# Risha_Mega_Shield.net
KiCad netlist of a schematic drawn in EAGLE
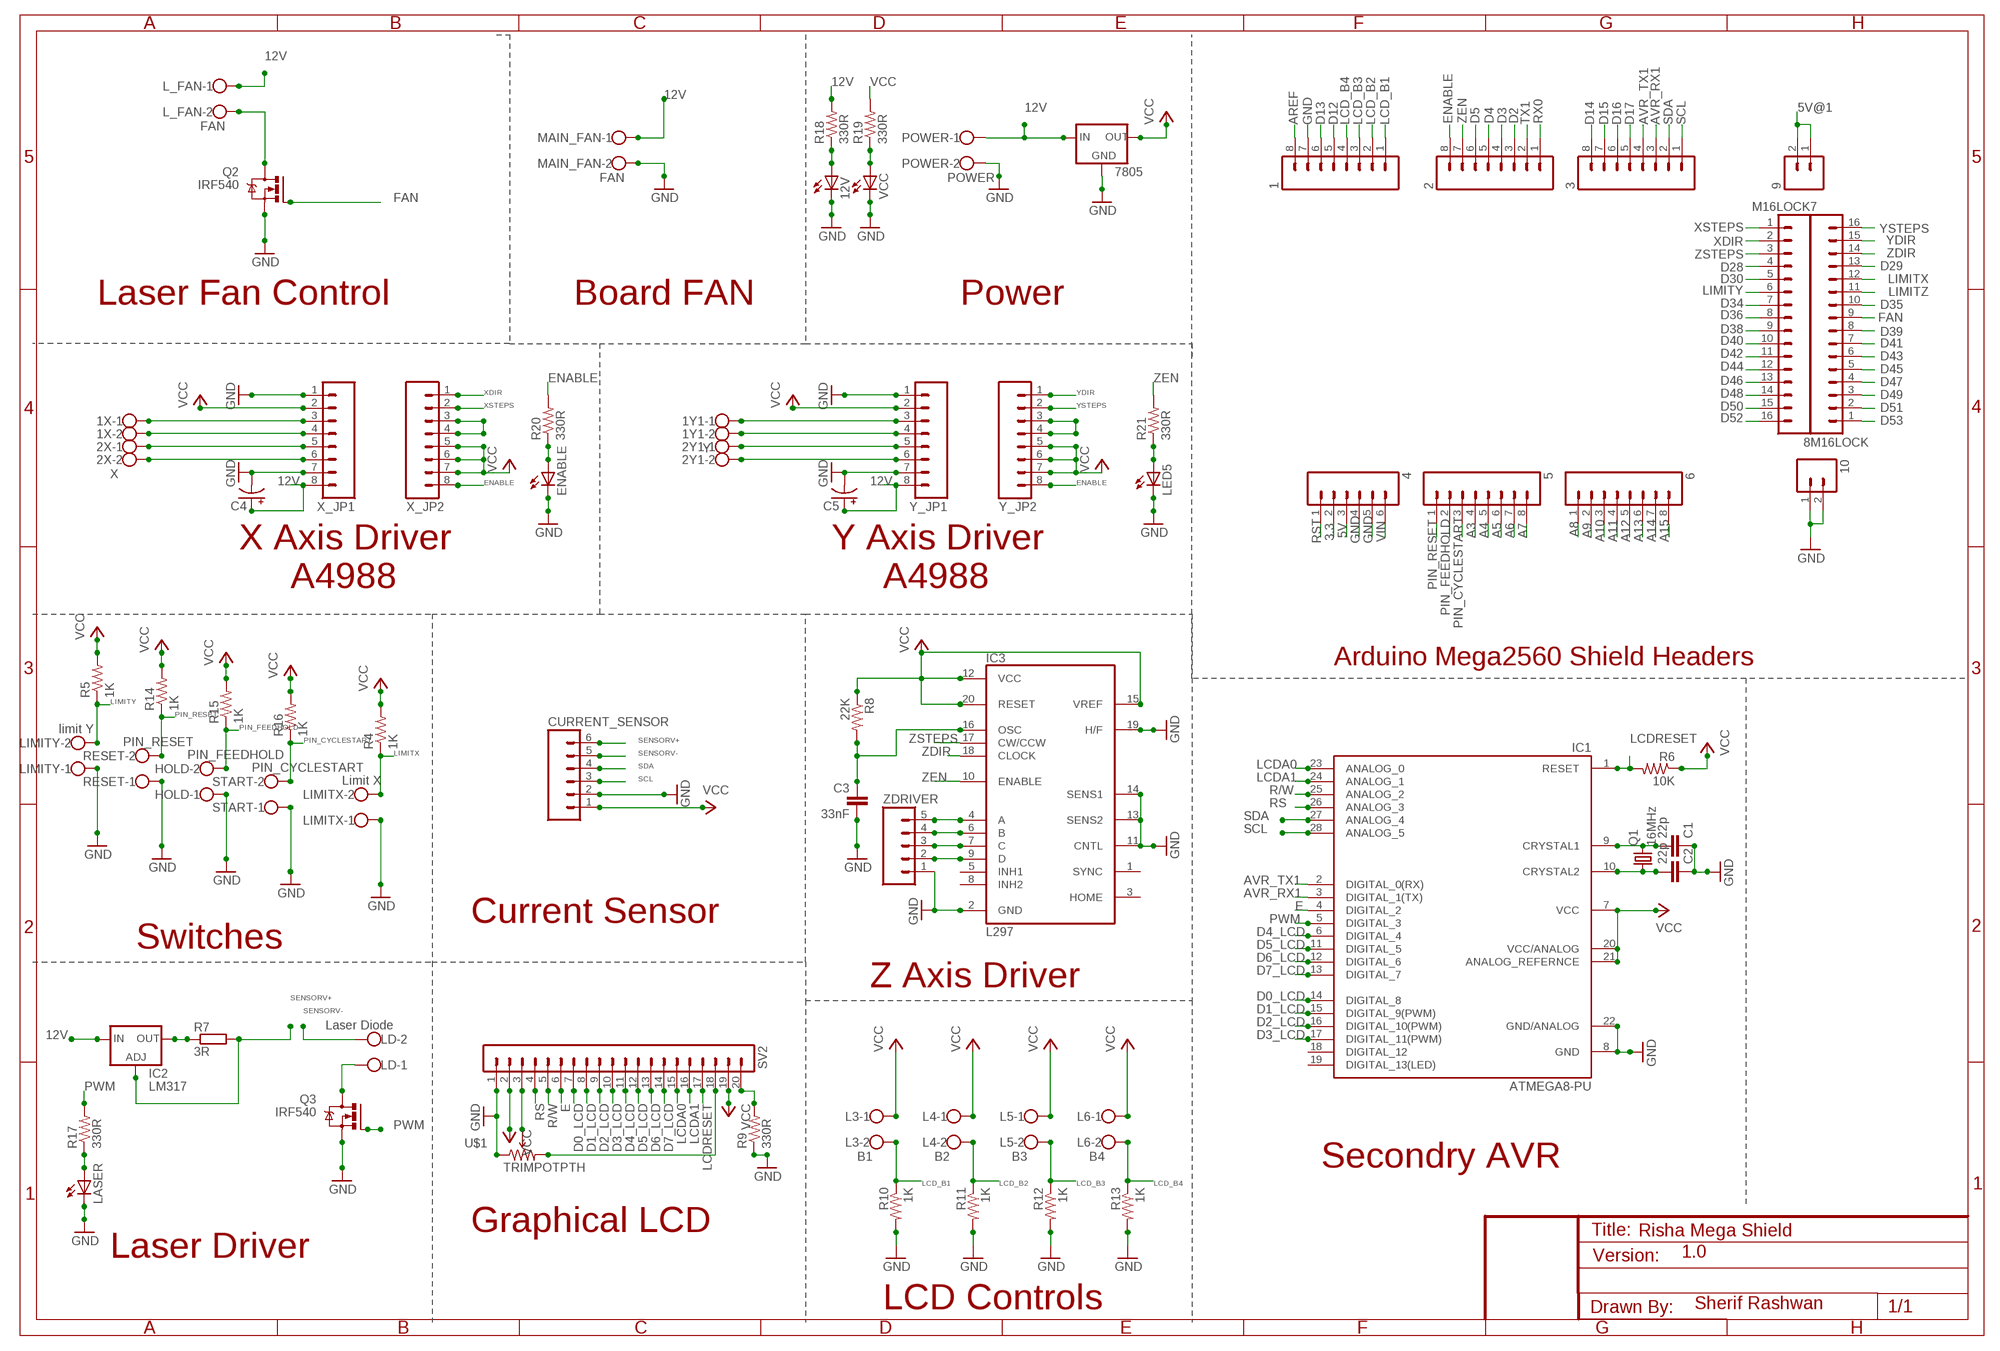
[diagram p0: schematic, sheet 1]

(export (version "E")
  (design (tool "Eeschema 10.0.6"))
  (components
    (comp (ref "1")
      (value "M08LOCK")
      (footprint "eagle-import:1X08_LOCK")
      (libsource (lib "eagle-import") (part "SparkFun_M08LOCK"))
    )
    (comp (ref "1X")
      (value "W237-102")
      (footprint "eagle-import:W237-102")
      (fields (field (name "MPN") "237-102"))
      (libsource (lib "eagle-import") (part "W237-102"))
    )
    (comp (ref "1Y1")
      (value "Y")
      (footprint "eagle-import:W237-102")
      (fields (field (name "MPN") "237-102"))
      (libsource (lib "eagle-import") (part "W237-102"))
    )
    (comp (ref "2")
      (value "M08LOCK")
      (footprint "eagle-import:1X08_LOCK")
      (libsource (lib "eagle-import") (part "SparkFun_M08LOCK"))
    )
    (comp (ref "2X")
      (value "X")
      (footprint "eagle-import:W237-102")
      (fields (field (name "MPN") "237-102"))
      (libsource (lib "eagle-import") (part "W237-102"))
    )
    (comp (ref "2Y1")
      (value "W237-102")
      (footprint "eagle-import:W237-102")
      (fields (field (name "MPN") "237-102"))
      (libsource (lib "eagle-import") (part "W237-102"))
    )
    (comp (ref "3")
      (value "M08LOCK")
      (footprint "eagle-import:1X08_LOCK")
      (libsource (lib "eagle-import") (part "SparkFun_M08LOCK"))
    )
    (comp (ref "4")
      (value "M06LOCK")
      (footprint "eagle-import:1X06_LOCK")
      (libsource (lib "eagle-import") (part "SparkFun_M06LOCK"))
    )
    (comp (ref "5")
      (value "M08LOCK")
      (footprint "eagle-import:1X08_LOCK")
      (libsource (lib "eagle-import") (part "SparkFun_M08LOCK"))
    )
    (comp (ref "6")
      (value "M08LOCK")
      (footprint "eagle-import:1X08_LOCK")
      (libsource (lib "eagle-import") (part "SparkFun_M08LOCK"))
    )
    (comp (ref "7")
      (value "M16LOCK")
      (footprint "eagle-import:1X16_LOCK")
      (libsource (lib "eagle-import") (part "M16LOCK"))
    )
    (comp (ref "8")
      (value "M16LOCK")
      (footprint "eagle-import:1X16_LOCK")
      (libsource (lib "eagle-import") (part "M16LOCK"))
    )
    (comp (ref "9")
      (value "M02LOCK")
      (footprint "eagle-import:1X02_LOCK")
      (libsource (lib "eagle-import") (part "M02LOCK"))
    )
    (comp (ref "10")
      (value "M02LOCK")
      (footprint "eagle-import:1X02_LOCK")
      (libsource (lib "eagle-import") (part "M02LOCK"))
    )
    (comp (ref "12V")
      (value "LED3MM")
      (footprint "eagle-import:LED3MM")
      (libsource (lib "eagle-import") (part "LED3MM"))
    )
    (comp (ref "7805")
      (value "V_REG_78XXSINK")
      (footprint "eagle-import:TO220-IGO")
      (libsource (lib "eagle-import") (part "V_REG_78XXSINK"))
    )
    (comp (ref "C1")
      (value "22p")
      (footprint "eagle-import:C2.5-2")
      (libsource (lib "eagle-import") (part "C2.5/2"))
    )
    (comp (ref "C2")
      (value "22p")
      (footprint "eagle-import:C2.5-2")
      (libsource (lib "eagle-import") (part "C2.5/2"))
    )
    (comp (ref "C3")
      (value "33nF")
      (footprint "eagle-import:C2.5-2")
      (libsource (lib "eagle-import") (part "C2.5/2"))
    )
    (comp (ref "C4")
      (value "CAP_POLPTH2")
      (footprint "eagle-import:CPOL-RADIAL-10UF-25V")
      (libsource (lib "eagle-import") (part "CAP_POLPTH2"))
    )
    (comp (ref "C5")
      (value "CAP_POLPTH2")
      (footprint "eagle-import:CPOL-RADIAL-10UF-25V")
      (libsource (lib "eagle-import") (part "CAP_POLPTH2"))
    )
    (comp (ref "CURRENT_SENSOR")
      (value "M06LONGPADS")
      (footprint "eagle-import:1X06_LONGPADS")
      (libsource (lib "eagle-import") (part "M06LONGPADS"))
    )
    (comp (ref "ENABLE")
      (value "LED3MM")
      (footprint "eagle-import:LED3MM")
      (libsource (lib "eagle-import") (part "LED3MM"))
    )
    (comp (ref "HOLD")
      (value "PIN_FEEDHOLD")
      (footprint "eagle-import:W237-102")
      (fields (field (name "MPN") "237-102"))
      (libsource (lib "eagle-import") (part "W237-102"))
    )
    (comp (ref "IC1")
      (value "ATMEGA8-PU")
      (footprint "eagle-import:DIL28-3")
      (libsource (lib "eagle-import") (part "ATMEGA8-PU"))
    )
    (comp (ref "IC2")
      (value "LM317")
      (footprint "eagle-import:TO3-K02")
      (libsource (lib "eagle-import") (part "LM317-TO3"))
    )
    (comp (ref "IC3")
      (value "L297")
      (footprint "eagle-import:DIL20")
      (fields (field (name "MPN") "L297/1"))
      (libsource (lib "eagle-import") (part "L297"))
    )
    (comp (ref "L3")
      (value "B1")
      (footprint "eagle-import:W237-102")
      (fields (field (name "MPN") "237-102"))
      (libsource (lib "eagle-import") (part "W237-102"))
    )
    (comp (ref "L4")
      (value "B2")
      (footprint "eagle-import:W237-102")
      (fields (field (name "MPN") "237-102"))
      (libsource (lib "eagle-import") (part "W237-102"))
    )
    (comp (ref "L5")
      (value "B3")
      (footprint "eagle-import:W237-102")
      (fields (field (name "MPN") "237-102"))
      (libsource (lib "eagle-import") (part "W237-102"))
    )
    (comp (ref "L6")
      (value "B4")
      (footprint "eagle-import:W237-102")
      (fields (field (name "MPN") "237-102"))
      (libsource (lib "eagle-import") (part "W237-102"))
    )
    (comp (ref "LASER")
      (value "LED3MM")
      (footprint "eagle-import:LED3MM")
      (libsource (lib "eagle-import") (part "LED3MM"))
    )
    (comp (ref "LD")
      (value "Laser Diode")
      (footprint "eagle-import:W237-102")
      (fields (field (name "MPN") "237-102"))
      (libsource (lib "eagle-import") (part "W237-102"))
    )
    (comp (ref "LED5")
      (value "LED3MM")
      (footprint "eagle-import:LED3MM")
      (libsource (lib "eagle-import") (part "LED3MM"))
    )
    (comp (ref "LIMITX")
      (value "Limit X")
      (footprint "eagle-import:W237-102")
      (fields (field (name "MPN") "237-102"))
      (libsource (lib "eagle-import") (part "W237-102"))
    )
    (comp (ref "LIMITY")
      (value "limit Y")
      (footprint "eagle-import:W237-102")
      (fields (field (name "MPN") "237-102"))
      (libsource (lib "eagle-import") (part "W237-102"))
    )
    (comp (ref "L_FAN")
      (value "FAN")
      (footprint "eagle-import:W237-102")
      (fields (field (name "MPN") "237-102"))
      (libsource (lib "eagle-import") (part "W237-102"))
    )
    (comp (ref "MAIN_FAN")
      (value "FAN")
      (footprint "eagle-import:W237-102")
      (fields (field (name "MPN") "237-102"))
      (libsource (lib "eagle-import") (part "W237-102"))
    )
    (comp (ref "POWER")
      (value "POWER")
      (footprint "eagle-import:W237-102")
      (fields (field (name "MPN") "237-102"))
      (libsource (lib "eagle-import") (part "W237-102"))
    )
    (comp (ref "Q1")
      (value "16MHz")
      (footprint "eagle-import:HC49US")
      (libsource (lib "eagle-import") (part "CRYSTALHC49US"))
    )
    (comp (ref "Q2")
      (value "IRF540")
      (footprint "eagle-import:TO220BV")
      (libsource (lib "eagle-import") (part "IRF540"))
    )
    (comp (ref "Q3")
      (value "IRF540")
      (footprint "eagle-import:TO220BV")
      (libsource (lib "eagle-import") (part "IRF540"))
    )
    (comp (ref "R4")
      (value "1K")
      (footprint "eagle-import:1_6W-RES")
      (libsource (lib "eagle-import") (part "RESISTORPTH-1/6W"))
    )
    (comp (ref "R5")
      (value "1K")
      (footprint "eagle-import:1_6W-RES")
      (libsource (lib "eagle-import") (part "RESISTORPTH-1/6W"))
    )
    (comp (ref "R6")
      (value "10K")
      (footprint "eagle-import:1_6W-RES")
      (libsource (lib "eagle-import") (part "RESISTORPTH-1/6W"))
    )
    (comp (ref "R7")
      (value "3R")
      (footprint "eagle-import:0309_12")
      (libsource (lib "eagle-import") (part "R-EU_0309/12"))
    )
    (comp (ref "R8")
      (value "22K")
      (footprint "eagle-import:1_6W-RES")
      (libsource (lib "eagle-import") (part "RESISTORPTH-1/6W"))
    )
    (comp (ref "R9")
      (value "330R")
      (footprint "eagle-import:1_6W-RES")
      (libsource (lib "eagle-import") (part "RESISTORPTH-1/6W"))
    )
    (comp (ref "R10")
      (value "1K")
      (footprint "eagle-import:1_6W-RES")
      (libsource (lib "eagle-import") (part "RESISTORPTH-1/6W"))
    )
    (comp (ref "R11")
      (value "1K")
      (footprint "eagle-import:1_6W-RES")
      (libsource (lib "eagle-import") (part "RESISTORPTH-1/6W"))
    )
    (comp (ref "R12")
      (value "1K")
      (footprint "eagle-import:1_6W-RES")
      (libsource (lib "eagle-import") (part "RESISTORPTH-1/6W"))
    )
    (comp (ref "R13")
      (value "1K")
      (footprint "eagle-import:1_6W-RES")
      (libsource (lib "eagle-import") (part "RESISTORPTH-1/6W"))
    )
    (comp (ref "R14")
      (value "1K")
      (footprint "eagle-import:1_6W-RES")
      (libsource (lib "eagle-import") (part "RESISTORPTH-1/6W"))
    )
    (comp (ref "R15")
      (value "1K")
      (footprint "eagle-import:1_6W-RES")
      (libsource (lib "eagle-import") (part "RESISTORPTH-1/6W"))
    )
    (comp (ref "R16")
      (value "1K")
      (footprint "eagle-import:1_6W-RES")
      (libsource (lib "eagle-import") (part "RESISTORPTH-1/6W"))
    )
    (comp (ref "R17")
      (value "330R")
      (footprint "eagle-import:1_6W-RES")
      (libsource (lib "eagle-import") (part "RESISTORPTH-1/6W"))
    )
    (comp (ref "R18")
      (value "330R")
      (footprint "eagle-import:1_6W-RES")
      (libsource (lib "eagle-import") (part "RESISTORPTH-1/6W"))
    )
    (comp (ref "R19")
      (value "330R")
      (footprint "eagle-import:1_6W-RES")
      (libsource (lib "eagle-import") (part "RESISTORPTH-1/6W"))
    )
    (comp (ref "R20")
      (value "330R")
      (footprint "eagle-import:1_6W-RES")
      (libsource (lib "eagle-import") (part "RESISTORPTH-1/6W"))
    )
    (comp (ref "R21")
      (value "330R")
      (footprint "eagle-import:1_6W-RES")
      (libsource (lib "eagle-import") (part "RESISTORPTH-1/6W"))
    )
    (comp (ref "RESET")
      (value "PIN_RESET")
      (footprint "eagle-import:W237-102")
      (fields (field (name "MPN") "237-102"))
      (libsource (lib "eagle-import") (part "W237-102"))
    )
    (comp (ref "START")
      (value "PIN_CYCLESTART")
      (footprint "eagle-import:W237-102")
      (fields (field (name "MPN") "237-102"))
      (libsource (lib "eagle-import") (part "W237-102"))
    )
    (comp (ref "SV2")
      (value "MA20-1W")
      (footprint "eagle-import:MA20-1W")
      (libsource (lib "eagle-import") (part "MA20-1W"))
    )
    (comp (ref "U$1")
      (value "TRIMPOTPTH")
      (footprint "eagle-import:TRIM_POT_PTH")
      (libsource (lib "eagle-import") (part "TRIMPOTPTH"))
    )
    (comp (ref "VCC")
      (value "LED3MM")
      (footprint "eagle-import:LED3MM")
      (libsource (lib "eagle-import") (part "LED3MM"))
    )
    (comp (ref "X_JP1")
      (value "M08")
      (footprint "eagle-import:1X08")
      (libsource (lib "eagle-import") (part "M08"))
    )
    (comp (ref "X_JP2")
      (value "M08")
      (footprint "eagle-import:1X08")
      (libsource (lib "eagle-import") (part "M08"))
    )
    (comp (ref "Y_JP1")
      (value "M08")
      (footprint "eagle-import:1X08")
      (libsource (lib "eagle-import") (part "M08"))
    )
    (comp (ref "Y_JP2")
      (value "M08")
      (footprint "eagle-import:1X08")
      (libsource (lib "eagle-import") (part "M08"))
    )
    (comp (ref "ZDRIVER")
      (value "M05PTH_LONGPADS")
      (footprint "eagle-import:1X05_LONGPADS")
      (libsource (lib "eagle-import") (part "M05PTH_LONGPADS"))
    )
  )
  (nets
    (net (code "1") (name "/3.3") (class "Default")
      (node (ref "4") (pin "2") (pinfunction "2_2") (pintype "passive"))
    )
    (net (code "2") (name "/5V") (class "Default")
      (node (ref "4") (pin "3") (pinfunction "3_3") (pintype "passive"))
    )
    (net (code "3") (name "/5V@1") (class "Default")
      (node (ref "9") (pin "1") (pinfunction "1_1") (pintype "passive"))
      (node (ref "9") (pin "2") (pinfunction "2_2") (pintype "passive"))
    )
    (net (code "4") (name "/12V") (class "Default")
      (node (ref "7805") (pin "IN") (pinfunction "IN_IN") (pintype "input"))
      (node (ref "C4") (pin "1") (pinfunction "+_1") (pintype "passive"))
      (node (ref "C5") (pin "1") (pinfunction "+_1") (pintype "passive"))
      (node (ref "IC2") (pin "1") (pinfunction "IN_1") (pintype "input"))
      (node (ref "L_FAN") (pin "1") (pinfunction "KL_1") (pintype "passive"))
      (node (ref "MAIN_FAN") (pin "1") (pinfunction "KL_1") (pintype "passive"))
      (node (ref "POWER") (pin "1") (pinfunction "KL_1") (pintype "passive"))
      (node (ref "R18") (pin "2") (pinfunction "2_2") (pintype "passive"))
      (node (ref "X_JP1") (pin "8") (pinfunction "8_8") (pintype "passive"))
      (node (ref "Y_JP1") (pin "8") (pinfunction "8_8") (pintype "passive"))
    )
    (net (code "5") (name "/A3") (class "Default")
      (node (ref "5") (pin "4") (pinfunction "4_4") (pintype "passive"))
    )
    (net (code "6") (name "/A4") (class "Default")
      (node (ref "5") (pin "5") (pinfunction "5_5") (pintype "passive"))
    )
    (net (code "7") (name "/A5") (class "Default")
      (node (ref "5") (pin "6") (pinfunction "6_6") (pintype "passive"))
    )
    (net (code "8") (name "/A6") (class "Default")
      (node (ref "5") (pin "7") (pinfunction "7_7") (pintype "passive"))
    )
    (net (code "9") (name "/A7") (class "Default")
      (node (ref "5") (pin "8") (pinfunction "8_8") (pintype "passive"))
    )
    (net (code "10") (name "/A8") (class "Default")
      (node (ref "6") (pin "1") (pinfunction "1_1") (pintype "passive"))
    )
    (net (code "11") (name "/A9") (class "Default")
      (node (ref "6") (pin "2") (pinfunction "2_2") (pintype "passive"))
    )
    (net (code "12") (name "/A10") (class "Default")
      (node (ref "6") (pin "3") (pinfunction "3_3") (pintype "passive"))
    )
    (net (code "13") (name "/A11") (class "Default")
      (node (ref "6") (pin "4") (pinfunction "4_4") (pintype "passive"))
    )
    (net (code "14") (name "/A12") (class "Default")
      (node (ref "6") (pin "5") (pinfunction "5_5") (pintype "passive"))
    )
    (net (code "15") (name "/A13") (class "Default")
      (node (ref "6") (pin "6") (pinfunction "6_6") (pintype "passive"))
    )
    (net (code "16") (name "/A14") (class "Default")
      (node (ref "6") (pin "7") (pinfunction "7_7") (pintype "passive"))
    )
    (net (code "17") (name "/A15") (class "Default")
      (node (ref "6") (pin "8") (pinfunction "8_8") (pintype "passive"))
    )
    (net (code "18") (name "/AREF") (class "Default")
      (node (ref "1") (pin "8") (pinfunction "8_8") (pintype "passive"))
    )
    (net (code "19") (name "/AVR_RX1") (class "Default")
      (node (ref "3") (pin "3") (pinfunction "3_3") (pintype "passive"))
      (node (ref "IC1") (pin "3") (pinfunction "DIGITAL_1(TX)_3") (pintype "bidirectional"))
    )
    (net (code "20") (name "/AVR_TX1") (class "Default")
      (node (ref "3") (pin "4") (pinfunction "4_4") (pintype "passive"))
      (node (ref "IC1") (pin "2") (pinfunction "DIGITAL_0(RX)_2") (pintype "bidirectional"))
    )
    (net (code "21") (name "/D0_LCD") (class "Default")
      (node (ref "IC1") (pin "14") (pinfunction "DIGITAL_8_14") (pintype "bidirectional"))
      (node (ref "SV2") (pin "7") (pinfunction "7_7") (pintype "passive"))
    )
    (net (code "22") (name "/D1_LCD") (class "Default")
      (node (ref "IC1") (pin "15") (pinfunction "DIGITAL_9(PWM)_15") (pintype "bidirectional"))
      (node (ref "SV2") (pin "8") (pinfunction "8_8") (pintype "passive"))
    )
    (net (code "23") (name "/D2") (class "Default")
      (node (ref "2") (pin "3") (pinfunction "3_3") (pintype "passive"))
    )
    (net (code "24") (name "/D2_LCD") (class "Default")
      (node (ref "IC1") (pin "16") (pinfunction "DIGITAL_10(PWM)_16") (pintype "bidirectional"))
      (node (ref "SV2") (pin "9") (pinfunction "9_9") (pintype "passive"))
    )
    (net (code "25") (name "/D3") (class "Default")
      (node (ref "2") (pin "4") (pinfunction "4_4") (pintype "passive"))
    )
    (net (code "26") (name "/D3_LCD") (class "Default")
      (node (ref "IC1") (pin "17") (pinfunction "DIGITAL_11(PWM)_17") (pintype "bidirectional"))
      (node (ref "SV2") (pin "10") (pinfunction "10_10") (pintype "passive"))
    )
    (net (code "27") (name "/D4") (class "Default")
      (node (ref "2") (pin "5") (pinfunction "5_5") (pintype "passive"))
    )
    (net (code "28") (name "/D4_LCD") (class "Default")
      (node (ref "IC1") (pin "6") (pinfunction "DIGITAL_4_6") (pintype "bidirectional"))
      (node (ref "SV2") (pin "11") (pinfunction "11_11") (pintype "passive"))
    )
    (net (code "29") (name "/D5") (class "Default")
      (node (ref "2") (pin "6") (pinfunction "6_6") (pintype "passive"))
    )
    (net (code "30") (name "/D5_LCD") (class "Default")
      (node (ref "IC1") (pin "11") (pinfunction "DIGITAL_5_11") (pintype "bidirectional"))
      (node (ref "SV2") (pin "12") (pinfunction "12_12") (pintype "passive"))
    )
    (net (code "31") (name "/D6_LCD") (class "Default")
      (node (ref "IC1") (pin "12") (pinfunction "DIGITAL_6_12") (pintype "bidirectional"))
      (node (ref "SV2") (pin "13") (pinfunction "13_13") (pintype "passive"))
    )
    (net (code "32") (name "/D7_LCD") (class "Default")
      (node (ref "IC1") (pin "13") (pinfunction "DIGITAL_7_13") (pintype "bidirectional"))
      (node (ref "SV2") (pin "14") (pinfunction "14_14") (pintype "passive"))
    )
    (net (code "33") (name "/D12") (class "Default")
      (node (ref "1") (pin "5") (pinfunction "5_5") (pintype "passive"))
    )
    (net (code "34") (name "/D13") (class "Default")
      (node (ref "1") (pin "6") (pinfunction "6_6") (pintype "passive"))
    )
    (net (code "35") (name "/D14") (class "Default")
      (node (ref "3") (pin "8") (pinfunction "8_8") (pintype "passive"))
    )
    (net (code "36") (name "/D15") (class "Default")
      (node (ref "3") (pin "7") (pinfunction "7_7") (pintype "passive"))
    )
    (net (code "37") (name "/D16") (class "Default")
      (node (ref "3") (pin "6") (pinfunction "6_6") (pintype "passive"))
    )
    (net (code "38") (name "/D17") (class "Default")
      (node (ref "3") (pin "5") (pinfunction "5_5") (pintype "passive"))
    )
    (net (code "39") (name "/D28") (class "Default")
      (node (ref "8") (pin "4") (pinfunction "4_4") (pintype "passive"))
    )
    (net (code "40") (name "/D29") (class "Default")
      (node (ref "7") (pin "13") (pinfunction "13_13") (pintype "passive"))
    )
    (net (code "41") (name "/D30") (class "Default")
      (node (ref "8") (pin "5") (pinfunction "5_5") (pintype "passive"))
    )
    (net (code "42") (name "/D34") (class "Default")
      (node (ref "8") (pin "7") (pinfunction "7_7") (pintype "passive"))
    )
    (net (code "43") (name "/D35") (class "Default")
      (node (ref "7") (pin "10") (pinfunction "10_10") (pintype "passive"))
    )
    (net (code "44") (name "/D36") (class "Default")
      (node (ref "8") (pin "8") (pinfunction "8_8") (pintype "passive"))
    )
    (net (code "45") (name "/D38") (class "Default")
      (node (ref "8") (pin "9") (pinfunction "9_9") (pintype "passive"))
    )
    (net (code "46") (name "/D39") (class "Default")
      (node (ref "7") (pin "8") (pinfunction "8_8") (pintype "passive"))
    )
    (net (code "47") (name "/D40") (class "Default")
      (node (ref "8") (pin "10") (pinfunction "10_10") (pintype "passive"))
    )
    (net (code "48") (name "/D41") (class "Default")
      (node (ref "7") (pin "7") (pinfunction "7_7") (pintype "passive"))
    )
    (net (code "49") (name "/D42") (class "Default")
      (node (ref "8") (pin "11") (pinfunction "11_11") (pintype "passive"))
    )
    (net (code "50") (name "/D43") (class "Default")
      (node (ref "7") (pin "6") (pinfunction "6_6") (pintype "passive"))
    )
    (net (code "51") (name "/D44") (class "Default")
      (node (ref "8") (pin "12") (pinfunction "12_12") (pintype "passive"))
    )
    (net (code "52") (name "/D45") (class "Default")
      (node (ref "7") (pin "5") (pinfunction "5_5") (pintype "passive"))
    )
    (net (code "53") (name "/D46") (class "Default")
      (node (ref "8") (pin "13") (pinfunction "13_13") (pintype "passive"))
    )
    (net (code "54") (name "/D47") (class "Default")
      (node (ref "7") (pin "4") (pinfunction "4_4") (pintype "passive"))
    )
    (net (code "55") (name "/D48") (class "Default")
      (node (ref "8") (pin "14") (pinfunction "14_14") (pintype "passive"))
    )
    (net (code "56") (name "/D49") (class "Default")
      (node (ref "7") (pin "3") (pinfunction "3_3") (pintype "passive"))
    )
    (net (code "57") (name "/D50") (class "Default")
      (node (ref "8") (pin "15") (pinfunction "15_15") (pintype "passive"))
    )
    (net (code "58") (name "/D51") (class "Default")
      (node (ref "7") (pin "2") (pinfunction "2_2") (pintype "passive"))
    )
    (net (code "59") (name "/D52") (class "Default")
      (node (ref "8") (pin "16") (pinfunction "16_16") (pintype "passive"))
    )
    (net (code "60") (name "/D53") (class "Default")
      (node (ref "7") (pin "1") (pinfunction "1_1") (pintype "passive"))
    )
    (net (code "61") (name "/E") (class "Default")
      (node (ref "IC1") (pin "4") (pinfunction "DIGITAL_2_4") (pintype "bidirectional"))
      (node (ref "SV2") (pin "6") (pinfunction "6_6") (pintype "passive"))
    )
    (net (code "62") (name "/ENABLE") (class "Default")
      (node (ref "2") (pin "8") (pinfunction "8_8") (pintype "passive"))
      (node (ref "R20") (pin "2") (pinfunction "2_2") (pintype "passive"))
      (node (ref "X_JP2") (pin "8") (pinfunction "8_8") (pintype "passive"))
      (node (ref "Y_JP2") (pin "8") (pinfunction "8_8") (pintype "passive"))
    )
    (net (code "63") (name "/FAN") (class "Default")
      (node (ref "7") (pin "9") (pinfunction "9_9") (pintype "passive"))
      (node (ref "Q2") (pin "G") (pinfunction "G_G") (pintype "passive"))
    )
    (net (code "64") (name "/LCDA0") (class "Default")
      (node (ref "IC1") (pin "23") (pinfunction "ANALOG_0_23") (pintype "bidirectional"))
      (node (ref "SV2") (pin "15") (pinfunction "15_15") (pintype "passive"))
    )
    (net (code "65") (name "/LCDA1") (class "Default")
      (node (ref "IC1") (pin "24") (pinfunction "ANALOG_1_24") (pintype "bidirectional"))
      (node (ref "SV2") (pin "16") (pinfunction "16_16") (pintype "passive"))
    )
    (net (code "66") (name "/LCDRESET") (class "Default")
      (node (ref "IC1") (pin "1") (pinfunction "RESET_1") (pintype "bidirectional"))
      (node (ref "R6") (pin "2") (pinfunction "2_2") (pintype "passive"))
      (node (ref "SV2") (pin "17") (pinfunction "17_17") (pintype "passive"))
    )
    (net (code "67") (name "/LCD_B1") (class "Default")
      (node (ref "1") (pin "1") (pinfunction "1_1") (pintype "passive"))
      (node (ref "L3") (pin "2") (pinfunction "KL_2") (pintype "passive"))
      (node (ref "R10") (pin "1") (pinfunction "1_1") (pintype "passive"))
    )
    (net (code "68") (name "/LCD_B2") (class "Default")
      (node (ref "1") (pin "2") (pinfunction "2_2") (pintype "passive"))
      (node (ref "L4") (pin "2") (pinfunction "KL_2") (pintype "passive"))
      (node (ref "R11") (pin "1") (pinfunction "1_1") (pintype "passive"))
    )
    (net (code "69") (name "/LCD_B3") (class "Default")
      (node (ref "1") (pin "3") (pinfunction "3_3") (pintype "passive"))
      (node (ref "L5") (pin "2") (pinfunction "KL_2") (pintype "passive"))
      (node (ref "R12") (pin "1") (pinfunction "1_1") (pintype "passive"))
    )
    (net (code "70") (name "/LCD_B4") (class "Default")
      (node (ref "1") (pin "4") (pinfunction "4_4") (pintype "passive"))
      (node (ref "L6") (pin "2") (pinfunction "KL_2") (pintype "passive"))
      (node (ref "R13") (pin "1") (pinfunction "1_1") (pintype "passive"))
    )
    (net (code "71") (name "/LIMITX") (class "Default")
      (node (ref "7") (pin "12") (pinfunction "12_12") (pintype "passive"))
      (node (ref "LIMITX") (pin "2") (pinfunction "KL_2") (pintype "passive"))
      (node (ref "R4") (pin "1") (pinfunction "1_1") (pintype "passive"))
    )
    (net (code "72") (name "/LIMITY") (class "Default")
      (node (ref "8") (pin "6") (pinfunction "6_6") (pintype "passive"))
      (node (ref "LIMITY") (pin "2") (pinfunction "KL_2") (pintype "passive"))
      (node (ref "R5") (pin "1") (pinfunction "1_1") (pintype "passive"))
    )
    (net (code "73") (name "/LIMITZ") (class "Default")
      (node (ref "7") (pin "11") (pinfunction "11_11") (pintype "passive"))
    )
    (net (code "74") (name "/PIN_CYCLESTART") (class "Default")
      (node (ref "5") (pin "3") (pinfunction "3_3") (pintype "passive"))
      (node (ref "R16") (pin "1") (pinfunction "1_1") (pintype "passive"))
      (node (ref "START") (pin "2") (pinfunction "KL_2") (pintype "passive"))
    )
    (net (code "75") (name "/PIN_FEEDHOLD") (class "Default")
      (node (ref "5") (pin "2") (pinfunction "2_2") (pintype "passive"))
      (node (ref "HOLD") (pin "2") (pinfunction "KL_2") (pintype "passive"))
      (node (ref "R15") (pin "1") (pinfunction "1_1") (pintype "passive"))
    )
    (net (code "76") (name "/PIN_RESET") (class "Default")
      (node (ref "5") (pin "1") (pinfunction "1_1") (pintype "passive"))
      (node (ref "R14") (pin "1") (pinfunction "1_1") (pintype "passive"))
      (node (ref "RESET") (pin "2") (pinfunction "KL_2") (pintype "passive"))
    )
    (net (code "77") (name "/PWM") (class "Default")
      (node (ref "IC1") (pin "5") (pinfunction "DIGITAL_3_5") (pintype "bidirectional"))
      (node (ref "Q3") (pin "G") (pinfunction "G_G") (pintype "passive"))
      (node (ref "R17") (pin "2") (pinfunction "2_2") (pintype "passive"))
    )
    (net (code "78") (name "/RS") (class "Default")
      (node (ref "IC1") (pin "26") (pinfunction "ANALOG_3_26") (pintype "bidirectional"))
      (node (ref "SV2") (pin "4") (pinfunction "4_4") (pintype "passive"))
    )
    (net (code "79") (name "/RST") (class "Default")
      (node (ref "4") (pin "1") (pinfunction "1_1") (pintype "passive"))
    )
    (net (code "80") (name "/RX0") (class "Default")
      (node (ref "2") (pin "1") (pinfunction "1_1") (pintype "passive"))
    )
    (net (code "81") (name "/R{slash}W") (class "Default")
      (node (ref "IC1") (pin "25") (pinfunction "ANALOG_2_25") (pintype "bidirectional"))
      (node (ref "SV2") (pin "5") (pinfunction "5_5") (pintype "passive"))
    )
    (net (code "82") (name "/SCL") (class "Default")
      (node (ref "3") (pin "1") (pinfunction "1_1") (pintype "passive"))
      (node (ref "CURRENT_SENSOR") (pin "3") (pinfunction "3_3") (pintype "passive"))
      (node (ref "IC1") (pin "28") (pinfunction "ANALOG_5_28") (pintype "bidirectional"))
    )
    (net (code "83") (name "/SDA") (class "Default")
      (node (ref "3") (pin "2") (pinfunction "2_2") (pintype "passive"))
      (node (ref "CURRENT_SENSOR") (pin "4") (pinfunction "4_4") (pintype "passive"))
      (node (ref "IC1") (pin "27") (pinfunction "ANALOG_4_27") (pintype "bidirectional"))
    )
    (net (code "84") (name "/SENSORV+") (class "Default")
      (node (ref "CURRENT_SENSOR") (pin "6") (pinfunction "6_6") (pintype "passive"))
      (node (ref "IC2") (pin "2") (pinfunction "ADJ_2") (pintype "input"))
      (node (ref "R7") (pin "2") (pinfunction "2_2") (pintype "passive"))
    )
    (net (code "85") (name "/SENSORV-") (class "Default")
      (node (ref "CURRENT_SENSOR") (pin "5") (pinfunction "5_5") (pintype "passive"))
      (node (ref "LD") (pin "2") (pinfunction "KL_2") (pintype "passive"))
    )
    (net (code "86") (name "/TX1") (class "Default")
      (node (ref "2") (pin "2") (pinfunction "2_2") (pintype "passive"))
    )
    (net (code "87") (name "/VIN") (class "Default")
      (node (ref "4") (pin "6") (pinfunction "6_6") (pintype "passive"))
    )
    (net (code "88") (name "/XDIR") (class "Default")
      (node (ref "8") (pin "2") (pinfunction "2_2") (pintype "passive"))
      (node (ref "X_JP2") (pin "1") (pinfunction "1_1") (pintype "passive"))
    )
    (net (code "89") (name "/XSTEPS") (class "Default")
      (node (ref "8") (pin "1") (pinfunction "1_1") (pintype "passive"))
      (node (ref "X_JP2") (pin "2") (pinfunction "2_2") (pintype "passive"))
    )
    (net (code "90") (name "/YDIR") (class "Default")
      (node (ref "7") (pin "15") (pinfunction "15_15") (pintype "passive"))
      (node (ref "Y_JP2") (pin "1") (pinfunction "1_1") (pintype "passive"))
    )
    (net (code "91") (name "/YSTEPS") (class "Default")
      (node (ref "7") (pin "16") (pinfunction "16_16") (pintype "passive"))
      (node (ref "Y_JP2") (pin "2") (pinfunction "2_2") (pintype "passive"))
    )
    (net (code "92") (name "/ZDIR") (class "Default")
      (node (ref "7") (pin "14") (pinfunction "14_14") (pintype "passive"))
      (node (ref "IC3") (pin "18") (pinfunction "CLOCK_18") (pintype "input"))
    )
    (net (code "93") (name "/ZEN") (class "Default")
      (node (ref "2") (pin "7") (pinfunction "7_7") (pintype "passive"))
      (node (ref "IC3") (pin "10") (pinfunction "ENABLE_10") (pintype "input"))
      (node (ref "R21") (pin "2") (pinfunction "2_2") (pintype "passive"))
    )
    (net (code "94") (name "/ZSTEPS") (class "Default")
      (node (ref "8") (pin "3") (pinfunction "3_3") (pintype "passive"))
      (node (ref "IC3") (pin "17") (pinfunction "CW/CCW_17") (pintype "input"))
    )
    (net (code "95") (name "GND") (class "Default")
      (node (ref "1") (pin "7") (pinfunction "7_7") (pintype "passive"))
      (node (ref "10") (pin "1") (pinfunction "1_1") (pintype "passive"))
      (node (ref "10") (pin "2") (pinfunction "2_2") (pintype "passive"))
      (node (ref "12V") (pin "K") (pinfunction "C_K") (pintype "passive"))
      (node (ref "4") (pin "4") (pinfunction "4_4") (pintype "passive"))
      (node (ref "4") (pin "5") (pinfunction "5_5") (pintype "passive"))
      (node (ref "7805") (pin "GND") (pinfunction "GND_GND") (pintype "input"))
      (node (ref "C1") (pin "1") (pinfunction "1_1") (pintype "passive"))
      (node (ref "C2") (pin "1") (pinfunction "1_1") (pintype "passive"))
      (node (ref "C3") (pin "2") (pinfunction "2_2") (pintype "passive"))
      (node (ref "C4") (pin "2") (pinfunction "-_2") (pintype "passive"))
      (node (ref "C5") (pin "2") (pinfunction "-_2") (pintype "passive"))
      (node (ref "CURRENT_SENSOR") (pin "2") (pinfunction "2_2") (pintype "passive"))
      (node (ref "ENABLE") (pin "K") (pinfunction "C_K") (pintype "passive"))
      (node (ref "HOLD") (pin "1") (pinfunction "KL_1") (pintype "passive"))
      (node (ref "IC1") (pin "22") (pinfunction "GND/ANALOG_22") (pintype "power_in"))
      (node (ref "IC1") (pin "8") (pinfunction "GND_8") (pintype "power_in"))
      (node (ref "IC3") (pin "11") (pinfunction "CNTL_11") (pintype "input"))
      (node (ref "IC3") (pin "13") (pinfunction "SENS2_13") (pintype "output"))
      (node (ref "IC3") (pin "14") (pinfunction "SENS1_14") (pintype "output"))
      (node (ref "IC3") (pin "19") (pinfunction "H/F_19") (pintype "input"))
      (node (ref "IC3") (pin "2") (pinfunction "GND_2") (pintype "power_in"))
      (node (ref "LASER") (pin "K") (pinfunction "C_K") (pintype "passive"))
      (node (ref "LED5") (pin "K") (pinfunction "C_K") (pintype "passive"))
      (node (ref "LIMITX") (pin "1") (pinfunction "KL_1") (pintype "passive"))
      (node (ref "LIMITY") (pin "1") (pinfunction "KL_1") (pintype "passive"))
      (node (ref "MAIN_FAN") (pin "2") (pinfunction "KL_2") (pintype "passive"))
      (node (ref "POWER") (pin "2") (pinfunction "KL_2") (pintype "passive"))
      (node (ref "Q2") (pin "S") (pinfunction "S_S") (pintype "passive"))
      (node (ref "Q3") (pin "S") (pinfunction "S_S") (pintype "passive"))
      (node (ref "R10") (pin "2") (pinfunction "2_2") (pintype "passive"))
      (node (ref "R11") (pin "2") (pinfunction "2_2") (pintype "passive"))
      (node (ref "R12") (pin "2") (pinfunction "2_2") (pintype "passive"))
      (node (ref "R13") (pin "2") (pinfunction "2_2") (pintype "passive"))
      (node (ref "R9") (pin "1") (pinfunction "1_1") (pintype "passive"))
      (node (ref "RESET") (pin "1") (pinfunction "KL_1") (pintype "passive"))
      (node (ref "START") (pin "1") (pinfunction "KL_1") (pintype "passive"))
      (node (ref "SV2") (pin "1") (pinfunction "1_1") (pintype "passive"))
      (node (ref "U$1") (pin "1") (pinfunction "CCW_1") (pintype "passive"))
      (node (ref "VCC") (pin "K") (pinfunction "C_K") (pintype "passive"))
      (node (ref "X_JP1") (pin "1") (pinfunction "1_1") (pintype "passive"))
      (node (ref "X_JP1") (pin "7") (pinfunction "7_7") (pintype "passive"))
      (node (ref "Y_JP1") (pin "1") (pinfunction "1_1") (pintype "passive"))
      (node (ref "Y_JP1") (pin "7") (pinfunction "7_7") (pintype "passive"))
      (node (ref "ZDRIVER") (pin "1") (pinfunction "1_1") (pintype "passive"))
    )
    (net (code "96") (name "Net-(1XA-KL)") (class "Default")
      (node (ref "1X") (pin "1") (pinfunction "KL_1") (pintype "passive"))
      (node (ref "X_JP1") (pin "3") (pinfunction "3_3") (pintype "passive"))
    )
    (net (code "97") (name "Net-(1XB-KL)") (class "Default")
      (node (ref "1X") (pin "2") (pinfunction "KL_2") (pintype "passive"))
      (node (ref "X_JP1") (pin "4") (pinfunction "4_4") (pintype "passive"))
    )
    (net (code "98") (name "Net-(1Y1A-KL)") (class "Default")
      (node (ref "1Y1") (pin "1") (pinfunction "KL_1") (pintype "passive"))
      (node (ref "Y_JP1") (pin "3") (pinfunction "3_3") (pintype "passive"))
    )
    (net (code "99") (name "Net-(1Y1B-KL)") (class "Default")
      (node (ref "1Y1") (pin "2") (pinfunction "KL_2") (pintype "passive"))
      (node (ref "Y_JP1") (pin "4") (pinfunction "4_4") (pintype "passive"))
    )
    (net (code "100") (name "Net-(2XA-KL)") (class "Default")
      (node (ref "2X") (pin "1") (pinfunction "KL_1") (pintype "passive"))
      (node (ref "X_JP1") (pin "5") (pinfunction "5_5") (pintype "passive"))
    )
    (net (code "101") (name "Net-(2XB-KL)") (class "Default")
      (node (ref "2X") (pin "2") (pinfunction "KL_2") (pintype "passive"))
      (node (ref "X_JP1") (pin "6") (pinfunction "6_6") (pintype "passive"))
    )
    (net (code "102") (name "Net-(2Y1A-KL)") (class "Default")
      (node (ref "2Y1") (pin "1") (pinfunction "KL_1") (pintype "passive"))
      (node (ref "Y_JP1") (pin "5") (pinfunction "5_5") (pintype "passive"))
    )
    (net (code "103") (name "Net-(2Y1B-KL)") (class "Default")
      (node (ref "2Y1") (pin "2") (pinfunction "KL_2") (pintype "passive"))
      (node (ref "Y_JP1") (pin "6") (pinfunction "6_6") (pintype "passive"))
    )
    (net (code "104") (name "Net-(12V-PadA)") (class "Default")
      (node (ref "12V") (pin "A") (pinfunction "A_A") (pintype "passive"))
      (node (ref "R18") (pin "1") (pinfunction "1_1") (pintype "passive"))
    )
    (net (code "105") (name "Net-(ENABLE-PadA)") (class "Default")
      (node (ref "ENABLE") (pin "A") (pinfunction "A_A") (pintype "passive"))
      (node (ref "R20") (pin "1") (pinfunction "1_1") (pintype "passive"))
    )
    (net (code "106") (name "Net-(IC1-CRYSTAL1)") (class "Default")
      (node (ref "C1") (pin "2") (pinfunction "2_2") (pintype "passive"))
      (node (ref "IC1") (pin "9") (pinfunction "CRYSTAL1_9") (pintype "bidirectional"))
      (node (ref "Q1") (pin "2") (pinfunction "2_2") (pintype "passive"))
    )
    (net (code "107") (name "Net-(IC1-CRYSTAL2)") (class "Default")
      (node (ref "C2") (pin "2") (pinfunction "2_2") (pintype "passive"))
      (node (ref "IC1") (pin "10") (pinfunction "CRYSTAL2_10") (pintype "bidirectional"))
      (node (ref "Q1") (pin "1") (pinfunction "1_1") (pintype "passive"))
    )
    (net (code "108") (name "Net-(IC2-OUT)") (class "Default")
      (node (ref "IC2") (pin "3") (pinfunction "OUT_3") (pintype "passive"))
      (node (ref "R7") (pin "1") (pinfunction "1_1") (pintype "passive"))
    )
    (net (code "109") (name "Net-(IC3-A)") (class "Default")
      (node (ref "IC3") (pin "4") (pinfunction "A_4") (pintype "output"))
      (node (ref "ZDRIVER") (pin "5") (pinfunction "5_5") (pintype "passive"))
    )
    (net (code "110") (name "Net-(IC3-B)") (class "Default")
      (node (ref "IC3") (pin "6") (pinfunction "B_6") (pintype "output"))
      (node (ref "ZDRIVER") (pin "4") (pinfunction "4_4") (pintype "passive"))
    )
    (net (code "111") (name "Net-(IC3-C)") (class "Default")
      (node (ref "IC3") (pin "7") (pinfunction "C_7") (pintype "output"))
      (node (ref "ZDRIVER") (pin "3") (pinfunction "3_3") (pintype "passive"))
    )
    (net (code "112") (name "Net-(IC3-D)") (class "Default")
      (node (ref "IC3") (pin "9") (pinfunction "D_9") (pintype "output"))
      (node (ref "ZDRIVER") (pin "2") (pinfunction "2_2") (pintype "passive"))
    )
    (net (code "113") (name "Net-(IC3-OSC)") (class "Default")
      (node (ref "C3") (pin "1") (pinfunction "1_1") (pintype "passive"))
      (node (ref "IC3") (pin "16") (pinfunction "OSC_16") (pintype "bidirectional"))
      (node (ref "R8") (pin "2") (pinfunction "2_2") (pintype "passive"))
    )
    (net (code "114") (name "Net-(LASER-PadA)") (class "Default")
      (node (ref "LASER") (pin "A") (pinfunction "A_A") (pintype "passive"))
      (node (ref "R17") (pin "1") (pinfunction "1_1") (pintype "passive"))
    )
    (net (code "115") (name "Net-(LDA-KL)") (class "Default")
      (node (ref "LD") (pin "1") (pinfunction "KL_1") (pintype "passive"))
      (node (ref "Q3") (pin "D") (pinfunction "D_D") (pintype "passive"))
    )
    (net (code "116") (name "Net-(LED5-PadA)") (class "Default")
      (node (ref "LED5") (pin "A") (pinfunction "A_A") (pintype "passive"))
      (node (ref "R21") (pin "1") (pinfunction "1_1") (pintype "passive"))
    )
    (net (code "117") (name "Net-(L_FANB-KL)") (class "Default")
      (node (ref "L_FAN") (pin "2") (pinfunction "KL_2") (pintype "passive"))
      (node (ref "Q2") (pin "D") (pinfunction "D_D") (pintype "passive"))
    )
    (net (code "118") (name "Net-(R9-Pad2)") (class "Default")
      (node (ref "R9") (pin "2") (pinfunction "2_2") (pintype "passive"))
      (node (ref "SV2") (pin "20") (pinfunction "20_20") (pintype "passive"))
    )
    (net (code "119") (name "Net-(R19-Pad1)") (class "Default")
      (node (ref "R19") (pin "1") (pinfunction "1_1") (pintype "passive"))
      (node (ref "VCC") (pin "A") (pinfunction "A_A") (pintype "passive"))
    )
    (net (code "120") (name "Net-(U$1-CW)") (class "Default")
      (node (ref "SV2") (pin "18") (pinfunction "18_18") (pintype "passive"))
      (node (ref "U$1") (pin "3") (pinfunction "CW_3") (pintype "passive"))
    )
    (net (code "121") (name "Net-(U$1-WIPER)") (class "Default")
      (node (ref "SV2") (pin "3") (pinfunction "3_3") (pintype "passive"))
      (node (ref "U$1") (pin "2") (pinfunction "WIPER_2") (pintype "passive"))
    )
    (net (code "122") (name "Net-(X_JP2-Pad3)") (class "Default")
      (node (ref "X_JP2") (pin "3") (pinfunction "3_3") (pintype "passive"))
      (node (ref "X_JP2") (pin "4") (pinfunction "4_4") (pintype "passive"))
    )
    (net (code "123") (name "Net-(Y_JP2-Pad3)") (class "Default")
      (node (ref "Y_JP2") (pin "3") (pinfunction "3_3") (pintype "passive"))
      (node (ref "Y_JP2") (pin "4") (pinfunction "4_4") (pintype "passive"))
    )
    (net (code "124") (name "VCC") (class "Default")
      (node (ref "7805") (pin "OUT") (pinfunction "OUT_OUT") (pintype "output"))
      (node (ref "CURRENT_SENSOR") (pin "1") (pinfunction "1_1") (pintype "passive"))
      (node (ref "IC1") (pin "20") (pinfunction "VCC/ANALOG_20") (pintype "passive"))
      (node (ref "IC1") (pin "21") (pinfunction "ANALOG_REFERNCE_21") (pintype "passive"))
      (node (ref "IC1") (pin "7") (pinfunction "VCC_7") (pintype "power_in"))
      (node (ref "IC3") (pin "12") (pinfunction "VCC_12") (pintype "power_in"))
      (node (ref "IC3") (pin "15") (pinfunction "VREF_15") (pintype "input"))
      (node (ref "IC3") (pin "20") (pinfunction "RESET_20") (pintype "input"))
      (node (ref "L3") (pin "1") (pinfunction "KL_1") (pintype "passive"))
      (node (ref "L4") (pin "1") (pinfunction "KL_1") (pintype "passive"))
      (node (ref "L5") (pin "1") (pinfunction "KL_1") (pintype "passive"))
      (node (ref "L6") (pin "1") (pinfunction "KL_1") (pintype "passive"))
      (node (ref "R14") (pin "2") (pinfunction "2_2") (pintype "passive"))
      (node (ref "R15") (pin "2") (pinfunction "2_2") (pintype "passive"))
      (node (ref "R16") (pin "2") (pinfunction "2_2") (pintype "passive"))
      (node (ref "R19") (pin "2") (pinfunction "2_2") (pintype "passive"))
      (node (ref "R4") (pin "2") (pinfunction "2_2") (pintype "passive"))
      (node (ref "R5") (pin "2") (pinfunction "2_2") (pintype "passive"))
      (node (ref "R6") (pin "1") (pinfunction "1_1") (pintype "passive"))
      (node (ref "R8") (pin "1") (pinfunction "1_1") (pintype "passive"))
      (node (ref "SV2") (pin "19") (pinfunction "19_19") (pintype "passive"))
      (node (ref "SV2") (pin "2") (pinfunction "2_2") (pintype "passive"))
      (node (ref "X_JP1") (pin "2") (pinfunction "2_2") (pintype "passive"))
      (node (ref "X_JP2") (pin "5") (pinfunction "5_5") (pintype "passive"))
      (node (ref "X_JP2") (pin "6") (pinfunction "6_6") (pintype "passive"))
      (node (ref "X_JP2") (pin "7") (pinfunction "7_7") (pintype "passive"))
      (node (ref "Y_JP1") (pin "2") (pinfunction "2_2") (pintype "passive"))
      (node (ref "Y_JP2") (pin "5") (pinfunction "5_5") (pintype "passive"))
      (node (ref "Y_JP2") (pin "6") (pinfunction "6_6") (pintype "passive"))
      (node (ref "Y_JP2") (pin "7") (pinfunction "7_7") (pintype "passive"))
    )
    (net (code "125") (name "unconnected-(IC1-DIGITAL_12-Pad18)") (class "Default")
      (node (ref "IC1") (pin "18") (pinfunction "DIGITAL_12_18") (pintype "bidirectional"))
    )
    (net (code "126") (name "unconnected-(IC1-DIGITAL_13(LED)-Pad19)") (class "Default")
      (node (ref "IC1") (pin "19") (pinfunction "DIGITAL_13(LED)_19") (pintype "bidirectional"))
    )
    (net (code "127") (name "unconnected-(IC3-HOME-Pad3)") (class "Default")
      (node (ref "IC3") (pin "3") (pinfunction "HOME_3") (pintype "output"))
    )
    (net (code "128") (name "unconnected-(IC3-INH1-Pad5)") (class "Default")
      (node (ref "IC3") (pin "5") (pinfunction "INH1_5") (pintype "output"))
    )
    (net (code "129") (name "unconnected-(IC3-INH2-Pad8)") (class "Default")
      (node (ref "IC3") (pin "8") (pinfunction "INH2_8") (pintype "output"))
    )
    (net (code "130") (name "unconnected-(IC3-SYNC-Pad1)") (class "Default")
      (node (ref "IC3") (pin "1") (pinfunction "SYNC_1") (pintype "output"))
    )
  )
)
